# current_sensor_transformer.net
KiCad netlist of a schematic drawn in Altium Designer
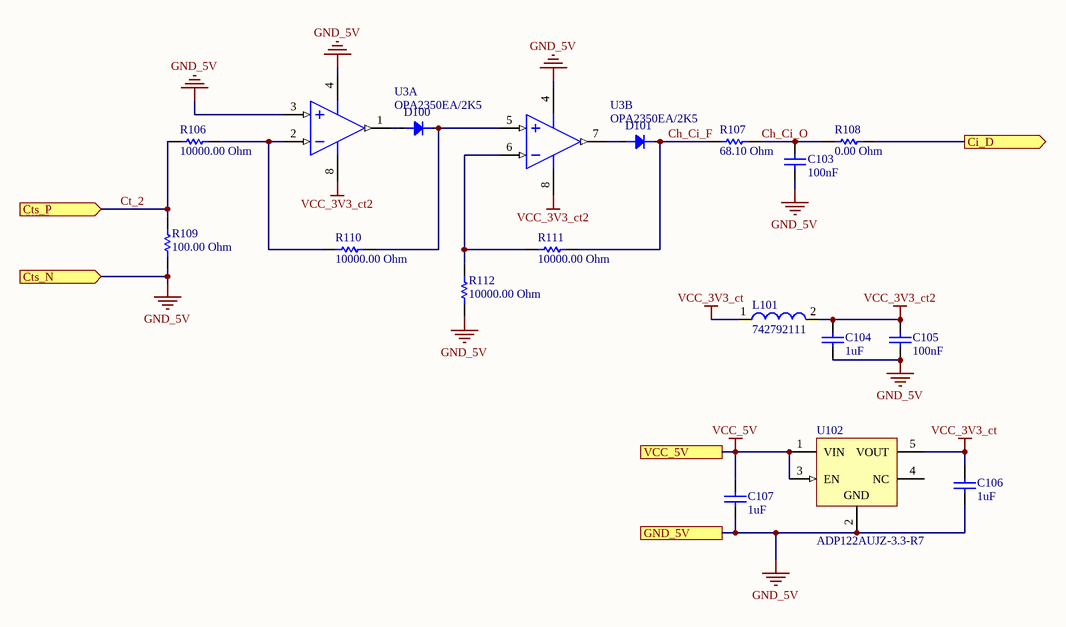
[diagram p0: current_sensor_transformer.SchDoc]

(export (version "E")
  (design (tool "Eeschema 10.0.6"))
  (components
    (comp (ref "C103")
      (value "100nF")
      (footprint "CAPC0603(1608)100_L")
      (description "CAP 100nF 10V ±10% 0603 (1608 Metric) Thickness 1mm SMD")
      (fields (field (name "TOLERANCE") "Â±10%") (field (name "Comment") "CAP 100nF 10V 0603(1608)"))
      (libsource (lib "Altium Content Vault") (part "CAP"))
    )
    (comp (ref "C104")
      (value "1uF")
      (footprint "CAPC0603(1608)100_L")
      (description "CAP 1uF 50V ±20% 0603 (1608 Metric) Thickness 1mm SMD")
      (fields (field (name "TOLERANCE") "Â±20%") (field (name "Comment") "CAP 1uF 50V 0603(1608)"))
      (libsource (lib "Altium Content Vault") (part "CAP"))
    )
    (comp (ref "C105")
      (value "100nF")
      (footprint "CAPC0603(1608)100_L")
      (description "CAP 100nF 10V ±10% 0603 (1608 Metric) Thickness 1mm SMD")
      (fields (field (name "TOLERANCE") "Â±10%") (field (name "Comment") "CAP 100nF 10V 0603(1608)"))
      (libsource (lib "Altium Content Vault") (part "CAP"))
    )
    (comp (ref "C106")
      (value "1uF")
      (footprint "CAPC0603(1608)100_N")
      (description "CAP 1uF 50V ±20% 0603 (1608 Metric) Thickness 1mm SMD")
      (fields (field (name "TOLERANCE") "Â±20%") (field (name "Comment") "CAP 1uF 50V 0603(1608)"))
      (libsource (lib "Altium Content Vault") (part "CAP"))
    )
    (comp (ref "C107")
      (value "1uF")
      (footprint "CAPC0603(1608)100_N")
      (description "CAP 1uF 50V ±20% 0603 (1608 Metric) Thickness 1mm SMD")
      (fields (field (name "TOLERANCE") "Â±20%") (field (name "Comment") "CAP 1uF 50V 0603(1608)"))
      (libsource (lib "Altium Content Vault") (part "CAP"))
    )
    (comp (ref "D100")
      (value "NRVB120VLSFT1G")
      (footprint "NRVB120VLSFT1G")
      (description "REEL / AUTO STANDARD OF MBR120VL")
      (fields (field (name "MANUFACTURER") "ON Semiconductor"))
      (libsource (lib "Diodes") (part "NRVB120VLSFT1G"))
    )
    (comp (ref "D101")
      (value "NRVB120VLSFT1G")
      (footprint "NRVB120VLSFT1G")
      (description "REEL / AUTO STANDARD OF MBR120VL")
      (fields (field (name "MANUFACTURER") "ON Semiconductor"))
      (libsource (lib "Diodes") (part "NRVB120VLSFT1G"))
    )
    (comp (ref "L101")
      (value "742792111")
      (footprint "SMD-1206")
      (description "SMD EMI Suppression Ferrite Bead WE-CBF, Z = 26 Ohm")
      (libsource (lib "Altium Content Vault") (part "PAS-IND-INDUCTOR-2"))
    )
    (comp (ref "R106")
      (value "10000.00 Ohm")
      (footprint "RESC1609X55X30LL15T15")
      (description "Chip Resistor, 10 KOhm, +/- 1%, 0.1 W, -55 to 155 degC, 0603 (1608 Metric), RoHS, Tape and Reel")
      (fields (field (name "TOLERANCE") "1%") (field (name "MANUFACTURER") "Panasonic"))
      (libsource (lib "Altium Content Vault") (part "RES-2"))
    )
    (comp (ref "R107")
      (value "68.10 Ohm")
      (footprint "RESC0805(2012)_L")
      (description "68R1 0.125W 1% 0805 (2012 Metric)  SMD")
      (fields (field (name "POWER") "0.125 W") (field (name "TOLERANCE") "1 %"))
      (libsource (lib "Altium Content Vault") (part "RES"))
    )
    (comp (ref "R108")
      (value "0.00 Ohm")
      (footprint "RESC0603(1608)_L")
      (description "Jumper 0603 (1608 Metric)")
      (fields (field (name "POWER") "None") (field (name "Comment") "Jumper 0603(1608)"))
      (libsource (lib "Altium Content Vault") (part "RES"))
    )
    (comp (ref "R109")
      (value "100.00 Ohm")
      (footprint "RESC1005X40X25NL05T05")
      (fields (field (name "PART NUMBER") "CRCW0402100RFKED") (field (name "MANUFACTURER") "Vishay Dale"))
      (libsource (lib "Altium Content Vault") (part "RES"))
    )
    (comp (ref "R110")
      (value "10000.00 Ohm")
      (footprint "RESC1609X55X30LL15T15")
      (description "Chip Resistor, 10 KOhm, +/- 1%, 0.1 W, -55 to 155 degC, 0603 (1608 Metric), RoHS, Tape and Reel")
      (fields (field (name "TOLERANCE") "1%") (field (name "MANUFACTURER") "Panasonic"))
      (libsource (lib "Altium Content Vault") (part "RES-2"))
    )
    (comp (ref "R111")
      (value "10000.00 Ohm")
      (footprint "RESC1609X55X30LL15T15")
      (description "Chip Resistor, 10 KOhm, +/- 1%, 0.1 W, -55 to 155 degC, 0603 (1608 Metric), RoHS, Tape and Reel")
      (fields (field (name "TOLERANCE") "1%") (field (name "MANUFACTURER") "Panasonic"))
      (libsource (lib "Altium Content Vault") (part "RES-2"))
    )
    (comp (ref "R112")
      (value "10000.00 Ohm")
      (footprint "RESC1609X55X30LL15T15")
      (description "Chip Resistor, 10 KOhm, +/- 1%, 0.1 W, -55 to 155 degC, 0603 (1608 Metric), RoHS, Tape and Reel")
      (fields (field (name "TOLERANCE") "1%") (field (name "MANUFACTURER") "Panasonic"))
      (libsource (lib "Altium Content Vault") (part "RES-2"))
    )
    (comp (ref "U3")
      (value "OPA2350EA/2K5")
      (footprint "DGK0008A_N")
      (fields (field (name "MANUFACTURER") "Texas Instruments"))
      (libsource (lib "Altium_Library_POWERLAB") (part "OPA2350EA/2K5"))
    )
    (comp (ref "U102")
      (value "ADP122AUJZ-3.3-R7")
      (footprint "ADI-UJ-5_L")
      (fields (field (name "MANUFACTURER") "Analog Devices"))
      (libsource (lib "Altium Content Vault") (part "ADI-ADP1XX-UJ-5"))
    )
  )
  (nets
    (net (code "1") (name "/Ch_Ci_F") (class "Default")
      (node (ref "D101") (pin "2") (pinfunction "2_2") (pintype "passive"))
      (node (ref "R107") (pin "2") (pinfunction "2_2") (pintype "passive"))
      (node (ref "R111") (pin "2") (pinfunction "2_2") (pintype "passive"))
    )
    (net (code "2") (name "/Ch_Ci_O") (class "Default")
      (node (ref "C103") (pin "2") (pinfunction "2_2") (pintype "passive"))
      (node (ref "R107") (pin "1") (pinfunction "1_1") (pintype "passive"))
      (node (ref "R108") (pin "2") (pinfunction "2_2") (pintype "passive"))
    )
    (net (code "3") (name "/Ci_D") (class "Default")
      (node (ref "R108") (pin "1") (pinfunction "1_1") (pintype "passive"))
    )
    (net (code "4") (name "/Ct_2") (class "Default")
      (node (ref "R106") (pin "2") (pinfunction "2_2") (pintype "passive"))
      (node (ref "R109") (pin "2") (pinfunction "2_2") (pintype "passive"))
    )
    (net (code "5") (name "GND_5V") (class "Default")
      (node (ref "C103") (pin "1") (pinfunction "1_1") (pintype "passive"))
      (node (ref "C104") (pin "1") (pinfunction "1_1") (pintype "passive"))
      (node (ref "C105") (pin "1") (pinfunction "1_1") (pintype "passive"))
      (node (ref "C106") (pin "1") (pinfunction "1_1") (pintype "passive"))
      (node (ref "C107") (pin "1") (pinfunction "1_1") (pintype "passive"))
      (node (ref "R109") (pin "1") (pinfunction "1_1") (pintype "passive"))
      (node (ref "R112") (pin "2") (pinfunction "2_2") (pintype "passive"))
      (node (ref "U102") (pin "2") (pinfunction "GND_2") (pintype "power_in"))
      (node (ref "U3") (pin "3") (pinfunction "IN_A+_3") (pintype "input"))
      (node (ref "U3") (pin "4") (pinfunction "V-_4") (pintype "power_in"))
    )
    (net (code "6") (name "Net-(U3A-IN_A-)") (class "Default")
      (node (ref "R106") (pin "1") (pinfunction "1_1") (pintype "passive"))
      (node (ref "R110") (pin "2") (pinfunction "2_2") (pintype "passive"))
      (node (ref "U3") (pin "2") (pinfunction "IN_A-_2") (pintype "input"))
    )
    (net (code "7") (name "Net-(U3A-OUT_A)") (class "Default")
      (node (ref "D100") (pin "1") (pinfunction "1_1") (pintype "passive"))
      (node (ref "U3") (pin "1") (pinfunction "OUT_A_1") (pintype "output"))
    )
    (net (code "8") (name "Net-(U3B-IN_B+)") (class "Default")
      (node (ref "D100") (pin "2") (pinfunction "2_2") (pintype "passive"))
      (node (ref "R110") (pin "1") (pinfunction "1_1") (pintype "passive"))
      (node (ref "U3") (pin "5") (pinfunction "IN_B+_5") (pintype "input"))
    )
    (net (code "9") (name "Net-(U3B-IN_B-)") (class "Default")
      (node (ref "R111") (pin "1") (pinfunction "1_1") (pintype "passive"))
      (node (ref "R112") (pin "1") (pinfunction "1_1") (pintype "passive"))
      (node (ref "U3") (pin "6") (pinfunction "IN_B-_6") (pintype "input"))
    )
    (net (code "10") (name "Net-(U3B-OUT_B)") (class "Default")
      (node (ref "D101") (pin "1") (pinfunction "1_1") (pintype "passive"))
      (node (ref "U3") (pin "7") (pinfunction "OUT_B_7") (pintype "output"))
    )
    (net (code "11") (name "VCC_3V3_ct") (class "Default")
      (node (ref "C106") (pin "2") (pinfunction "2_2") (pintype "passive"))
      (node (ref "L101") (pin "1") (pinfunction "1_1") (pintype "passive"))
      (node (ref "U102") (pin "5") (pinfunction "VOUT_5") (pintype "power_in"))
    )
    (net (code "12") (name "VCC_3V3_ct2") (class "Default")
      (node (ref "C104") (pin "2") (pinfunction "2_2") (pintype "passive"))
      (node (ref "C105") (pin "2") (pinfunction "2_2") (pintype "passive"))
      (node (ref "L101") (pin "2") (pinfunction "2_2") (pintype "passive"))
      (node (ref "U3") (pin "8") (pinfunction "V+_8") (pintype "power_in"))
    )
    (net (code "13") (name "VCC_5V") (class "Default")
      (node (ref "C107") (pin "2") (pinfunction "2_2") (pintype "passive"))
      (node (ref "U102") (pin "1") (pinfunction "VIN_1") (pintype "power_in"))
      (node (ref "U102") (pin "3") (pinfunction "EN_3") (pintype "input"))
    )
    (net (code "14") (name "unconnected-(U102-NC-Pad4)") (class "Default")
      (node (ref "U102") (pin "4") (pinfunction "NC_4") (pintype "passive"))
    )
  )
)
